# Microcontroller.net
KiCad netlist of a schematic drawn in Altium Designer
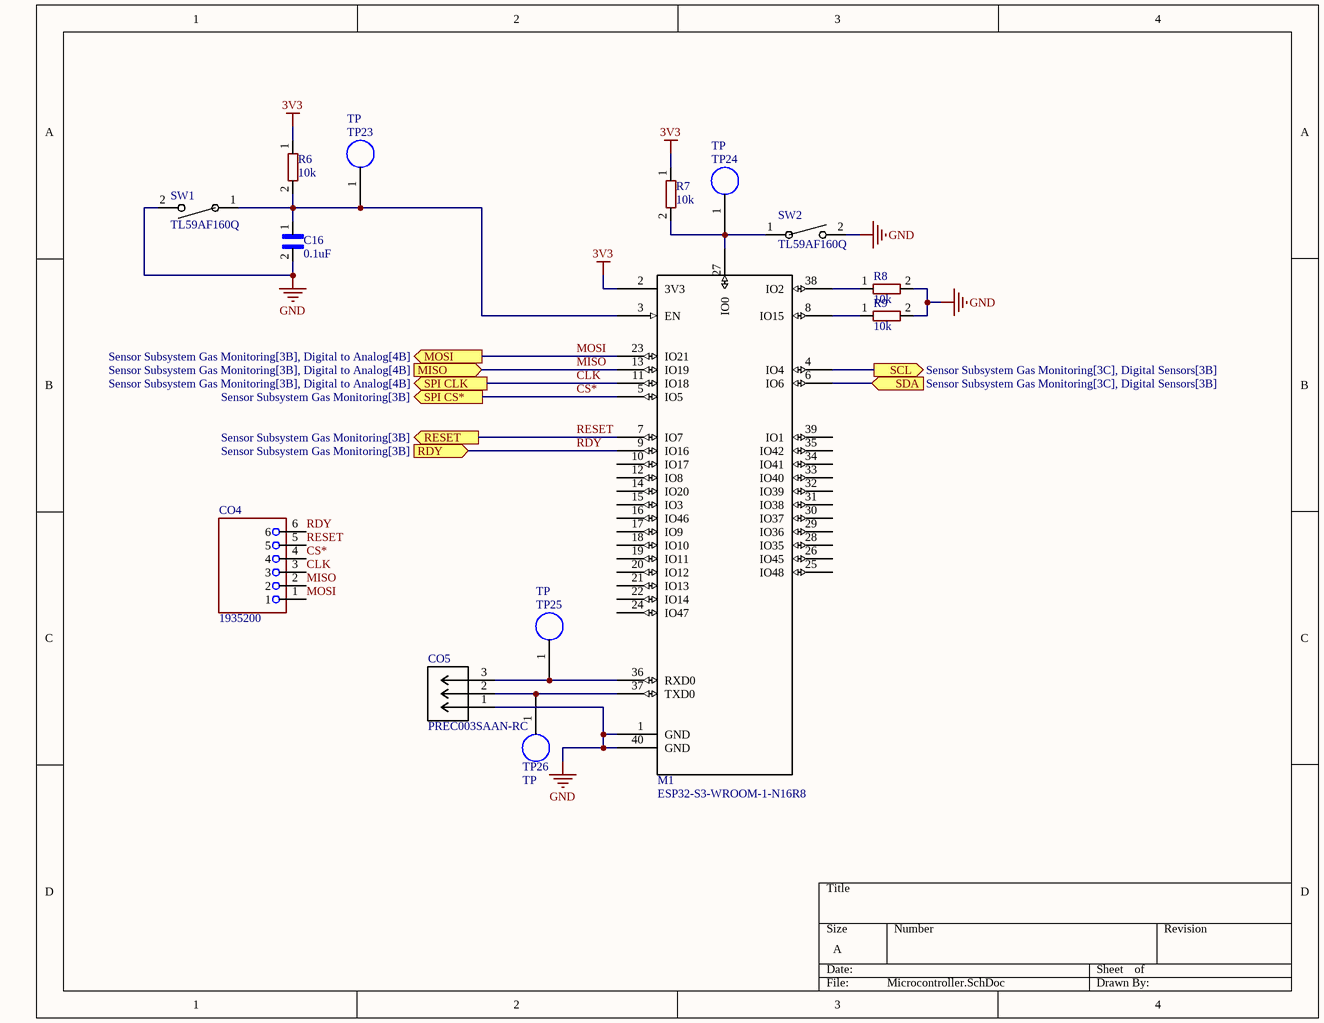
[diagram p0: Microcontroller.SchDoc]

(export (version "E")
  (design (tool "Eeschema 10.0.6"))
  (components
    (comp (ref "C16")
      (value "0.1uF")
      (footprint "0.1uF Capacitor")
      (description "No Description Available")
      (libsource (lib "0.1uF Capacitor") (part "CC1206JRX7R9BB104"))
    )
    (comp (ref "CO4")
      (value "1935200")
      (footprint "PHOENIX_1935200")
      (fields (field (name "MF") "Littelfuse"))
      (libsource (lib "Main Connector") (part "1935200"))
    )
    (comp (ref "CO5")
      (value "PREC003SAAN-RC")
      (footprint "CONN_PREC003SAAN-RC_SUL")
      (description "No Description Available")
      (libsource (lib "USB Connector") (part "PREC003SAAN-RC"))
    )
    (comp (ref "M1")
      (value "ESP32-S3-WROOM-1-N16R8")
      (footprint "ESP32-S3-WROOM-1_EXP")
      (description "No Description Available")
      (libsource (lib "ESP32-S3-WROOM-1-N16R8") (part "ESP32-S3-WROOM-1-N16R8"))
    )
    (comp (ref "R6")
      (value "10k")
      (footprint "10K Resistor:0603")
      (description "http://octopart.com/rc0603fr-1310kl-yageo+%2F+phycomp-25905087")
      (fields (field (name "MP") "RC0603FR-1310KL"))
      (libsource (lib "10K Resistor") (part "RC0603FR-1310KL"))
    )
    (comp (ref "R7")
      (value "10k")
      (footprint "10K Resistor:0603")
      (description "http://octopart.com/rc0603fr-1310kl-yageo+%2F+phycomp-25905087")
      (fields (field (name "MP") "RC0603FR-1310KL"))
      (libsource (lib "10K Resistor") (part "RC0603FR-1310KL"))
    )
    (comp (ref "R8")
      (value "10k")
      (footprint "10K Resistor:0603")
      (description "http://octopart.com/rc0603fr-1310kl-yageo+%2F+phycomp-25905087")
      (fields (field (name "MP") "RC0603FR-1310KL"))
      (libsource (lib "") (part "RC0603FR-1310KL_1"))
    )
    (comp (ref "R9")
      (value "10k")
      (footprint "10K Resistor:0603")
      (description "http://octopart.com/rc0603fr-1310kl-yageo+%2F+phycomp-25905087")
      (fields (field (name "MP") "RC0603FR-1310KL"))
      (libsource (lib "") (part "RC0603FR-1310KL_1"))
    )
    (comp (ref "SW1")
      (value "TL59AF160Q")
      (footprint "SW_TL59AF160Q_EWI")
      (description "No Description Available")
      (libsource (lib "") (part "TL59AF160Q_1"))
    )
    (comp (ref "SW2")
      (value "TL59AF160Q")
      (footprint "SW_TL59AF160Q_EWI")
      (description "No Description Available")
      (libsource (lib "Push Button") (part "TL59AF160Q"))
    )
    (comp (ref "TP23")
      (value "TP")
      (footprint "TestPoint")
      (description "Test point for voltage, current, ect.")
      (libsource (lib "TestPoint") (part "TestPoint"))
    )
    (comp (ref "TP24")
      (value "TP")
      (footprint "TestPoint")
      (description "Test point for voltage, current, ect.")
      (libsource (lib "TestPoint") (part "TestPoint"))
    )
    (comp (ref "TP25")
      (value "TP")
      (footprint "TestPoint")
      (description "Test point for voltage, current, ect.")
      (libsource (lib "TestPoint") (part "TestPoint"))
    )
    (comp (ref "TP26")
      (value "TP")
      (footprint "TestPoint")
      (description "Test point for voltage, current, ect.")
      (libsource (lib "TestPoint") (part "TestPoint"))
    )
  )
  (nets
    (net (code "1") (name "/CLK") (class "Default")
      (node (ref "CO4") (pin "3") (pinfunction "3_3") (pintype "passive"))
      (node (ref "M1") (pin "11") (pinfunction "IO18_11") (pintype "bidirectional"))
    )
    (net (code "2") (name "/CS*") (class "Default")
      (node (ref "CO4") (pin "4") (pinfunction "4_4") (pintype "passive"))
      (node (ref "M1") (pin "5") (pinfunction "IO5_5") (pintype "bidirectional"))
    )
    (net (code "3") (name "/MISO") (class "Default")
      (node (ref "CO4") (pin "2") (pinfunction "2_2") (pintype "passive"))
      (node (ref "M1") (pin "13") (pinfunction "IO19_13") (pintype "bidirectional"))
    )
    (net (code "4") (name "/MOSI") (class "Default")
      (node (ref "CO4") (pin "1") (pinfunction "1_1") (pintype "passive"))
      (node (ref "M1") (pin "23") (pinfunction "IO21_23") (pintype "bidirectional"))
    )
    (net (code "5") (name "/RDY") (class "Default")
      (node (ref "CO4") (pin "6") (pinfunction "6_6") (pintype "passive"))
      (node (ref "M1") (pin "9") (pinfunction "IO16_9") (pintype "bidirectional"))
    )
    (net (code "6") (name "/RESET") (class "Default")
      (node (ref "CO4") (pin "5") (pinfunction "5_5") (pintype "passive"))
      (node (ref "M1") (pin "7") (pinfunction "IO7_7") (pintype "bidirectional"))
    )
    (net (code "7") (name "/SCL") (class "Default")
      (node (ref "M1") (pin "4") (pinfunction "IO4_4") (pintype "bidirectional"))
    )
    (net (code "8") (name "/SDA") (class "Default")
      (node (ref "M1") (pin "6") (pinfunction "IO6_6") (pintype "bidirectional"))
    )
    (net (code "9") (name "3V3") (class "Default")
      (node (ref "M1") (pin "2") (pinfunction "3V3_2") (pintype "power_in"))
      (node (ref "R6") (pin "1") (pintype "passive"))
      (node (ref "R7") (pin "1") (pintype "passive"))
    )
    (net (code "10") (name "GND") (class "Default")
      (node (ref "C16") (pin "2") (pintype "passive"))
      (node (ref "CO5") (pin "1") (pinfunction "1_1") (pintype "passive"))
      (node (ref "M1") (pin "1") (pinfunction "GND_1") (pintype "power_in"))
      (node (ref "M1") (pin "40") (pinfunction "GND_40") (pintype "power_in"))
      (node (ref "R8") (pin "2") (pintype "passive"))
      (node (ref "R9") (pin "2") (pintype "passive"))
      (node (ref "SW1") (pin "2") (pinfunction "2_2") (pintype "passive"))
      (node (ref "SW2") (pin "2") (pinfunction "2_2") (pintype "passive"))
    )
    (net (code "11") (name "Net-(M1-EN)") (class "Default")
      (node (ref "C16") (pin "1") (pintype "passive"))
      (node (ref "M1") (pin "3") (pinfunction "EN_3") (pintype "input"))
      (node (ref "R6") (pin "2") (pintype "passive"))
      (node (ref "SW1") (pin "1") (pinfunction "1_1") (pintype "passive"))
      (node (ref "TP23") (pin "1") (pintype "passive"))
    )
    (net (code "12") (name "Net-(M1-IO0)") (class "Default")
      (node (ref "M1") (pin "27") (pinfunction "IO0_27") (pintype "bidirectional"))
      (node (ref "R7") (pin "2") (pintype "passive"))
      (node (ref "SW2") (pin "1") (pinfunction "1_1") (pintype "passive"))
      (node (ref "TP24") (pin "1") (pintype "passive"))
    )
    (net (code "13") (name "Net-(M1-IO2)") (class "Default")
      (node (ref "M1") (pin "38") (pinfunction "IO2_38") (pintype "bidirectional"))
      (node (ref "R8") (pin "1") (pintype "passive"))
    )
    (net (code "14") (name "Net-(M1-IO15)") (class "Default")
      (node (ref "M1") (pin "8") (pinfunction "IO15_8") (pintype "bidirectional"))
      (node (ref "R9") (pin "1") (pintype "passive"))
    )
    (net (code "15") (name "Net-(M1-RXD0)") (class "Default")
      (node (ref "CO5") (pin "3") (pinfunction "3_3") (pintype "passive"))
      (node (ref "M1") (pin "36") (pinfunction "RXD0_36") (pintype "bidirectional"))
      (node (ref "TP25") (pin "1") (pintype "passive"))
    )
    (net (code "16") (name "Net-(M1-TXD0)") (class "Default")
      (node (ref "CO5") (pin "2") (pinfunction "2_2") (pintype "passive"))
      (node (ref "M1") (pin "37") (pinfunction "TXD0_37") (pintype "bidirectional"))
      (node (ref "TP26") (pin "1") (pintype "passive"))
    )
    (net (code "17") (name "unconnected-(M1-IO1-Pad39)") (class "Default")
      (node (ref "M1") (pin "39") (pinfunction "IO1_39") (pintype "bidirectional"))
    )
    (net (code "18") (name "unconnected-(M1-IO3-Pad15)") (class "Default")
      (node (ref "M1") (pin "15") (pinfunction "IO3_15") (pintype "bidirectional"))
    )
    (net (code "19") (name "unconnected-(M1-IO8-Pad12)") (class "Default")
      (node (ref "M1") (pin "12") (pinfunction "IO8_12") (pintype "bidirectional"))
    )
    (net (code "20") (name "unconnected-(M1-IO9-Pad17)") (class "Default")
      (node (ref "M1") (pin "17") (pinfunction "IO9_17") (pintype "bidirectional"))
    )
    (net (code "21") (name "unconnected-(M1-IO10-Pad18)") (class "Default")
      (node (ref "M1") (pin "18") (pinfunction "IO10_18") (pintype "bidirectional"))
    )
    (net (code "22") (name "unconnected-(M1-IO11-Pad19)") (class "Default")
      (node (ref "M1") (pin "19") (pinfunction "IO11_19") (pintype "bidirectional"))
    )
    (net (code "23") (name "unconnected-(M1-IO12-Pad20)") (class "Default")
      (node (ref "M1") (pin "20") (pinfunction "IO12_20") (pintype "bidirectional"))
    )
    (net (code "24") (name "unconnected-(M1-IO13-Pad21)") (class "Default")
      (node (ref "M1") (pin "21") (pinfunction "IO13_21") (pintype "bidirectional"))
    )
    (net (code "25") (name "unconnected-(M1-IO14-Pad22)") (class "Default")
      (node (ref "M1") (pin "22") (pinfunction "IO14_22") (pintype "bidirectional"))
    )
    (net (code "26") (name "unconnected-(M1-IO17-Pad10)") (class "Default")
      (node (ref "M1") (pin "10") (pinfunction "IO17_10") (pintype "bidirectional"))
    )
    (net (code "27") (name "unconnected-(M1-IO20-Pad14)") (class "Default")
      (node (ref "M1") (pin "14") (pinfunction "IO20_14") (pintype "bidirectional"))
    )
    (net (code "28") (name "unconnected-(M1-IO35-Pad28)") (class "Default")
      (node (ref "M1") (pin "28") (pinfunction "IO35_28") (pintype "bidirectional"))
    )
    (net (code "29") (name "unconnected-(M1-IO36-Pad29)") (class "Default")
      (node (ref "M1") (pin "29") (pinfunction "IO36_29") (pintype "bidirectional"))
    )
    (net (code "30") (name "unconnected-(M1-IO37-Pad30)") (class "Default")
      (node (ref "M1") (pin "30") (pinfunction "IO37_30") (pintype "bidirectional"))
    )
    (net (code "31") (name "unconnected-(M1-IO38-Pad31)") (class "Default")
      (node (ref "M1") (pin "31") (pinfunction "IO38_31") (pintype "bidirectional"))
    )
    (net (code "32") (name "unconnected-(M1-IO39-Pad32)") (class "Default")
      (node (ref "M1") (pin "32") (pinfunction "IO39_32") (pintype "bidirectional"))
    )
    (net (code "33") (name "unconnected-(M1-IO40-Pad33)") (class "Default")
      (node (ref "M1") (pin "33") (pinfunction "IO40_33") (pintype "bidirectional"))
    )
    (net (code "34") (name "unconnected-(M1-IO41-Pad34)") (class "Default")
      (node (ref "M1") (pin "34") (pinfunction "IO41_34") (pintype "bidirectional"))
    )
    (net (code "35") (name "unconnected-(M1-IO42-Pad35)") (class "Default")
      (node (ref "M1") (pin "35") (pinfunction "IO42_35") (pintype "bidirectional"))
    )
    (net (code "36") (name "unconnected-(M1-IO45-Pad26)") (class "Default")
      (node (ref "M1") (pin "26") (pinfunction "IO45_26") (pintype "bidirectional"))
    )
    (net (code "37") (name "unconnected-(M1-IO46-Pad16)") (class "Default")
      (node (ref "M1") (pin "16") (pinfunction "IO46_16") (pintype "bidirectional"))
    )
    (net (code "38") (name "unconnected-(M1-IO47-Pad24)") (class "Default")
      (node (ref "M1") (pin "24") (pinfunction "IO47_24") (pintype "bidirectional"))
    )
    (net (code "39") (name "unconnected-(M1-IO48-Pad25)") (class "Default")
      (node (ref "M1") (pin "25") (pinfunction "IO48_25") (pintype "bidirectional"))
    )
  )
)
